# gps-to-spi.net
KiCad netlist of a schematic drawn in EAGLE
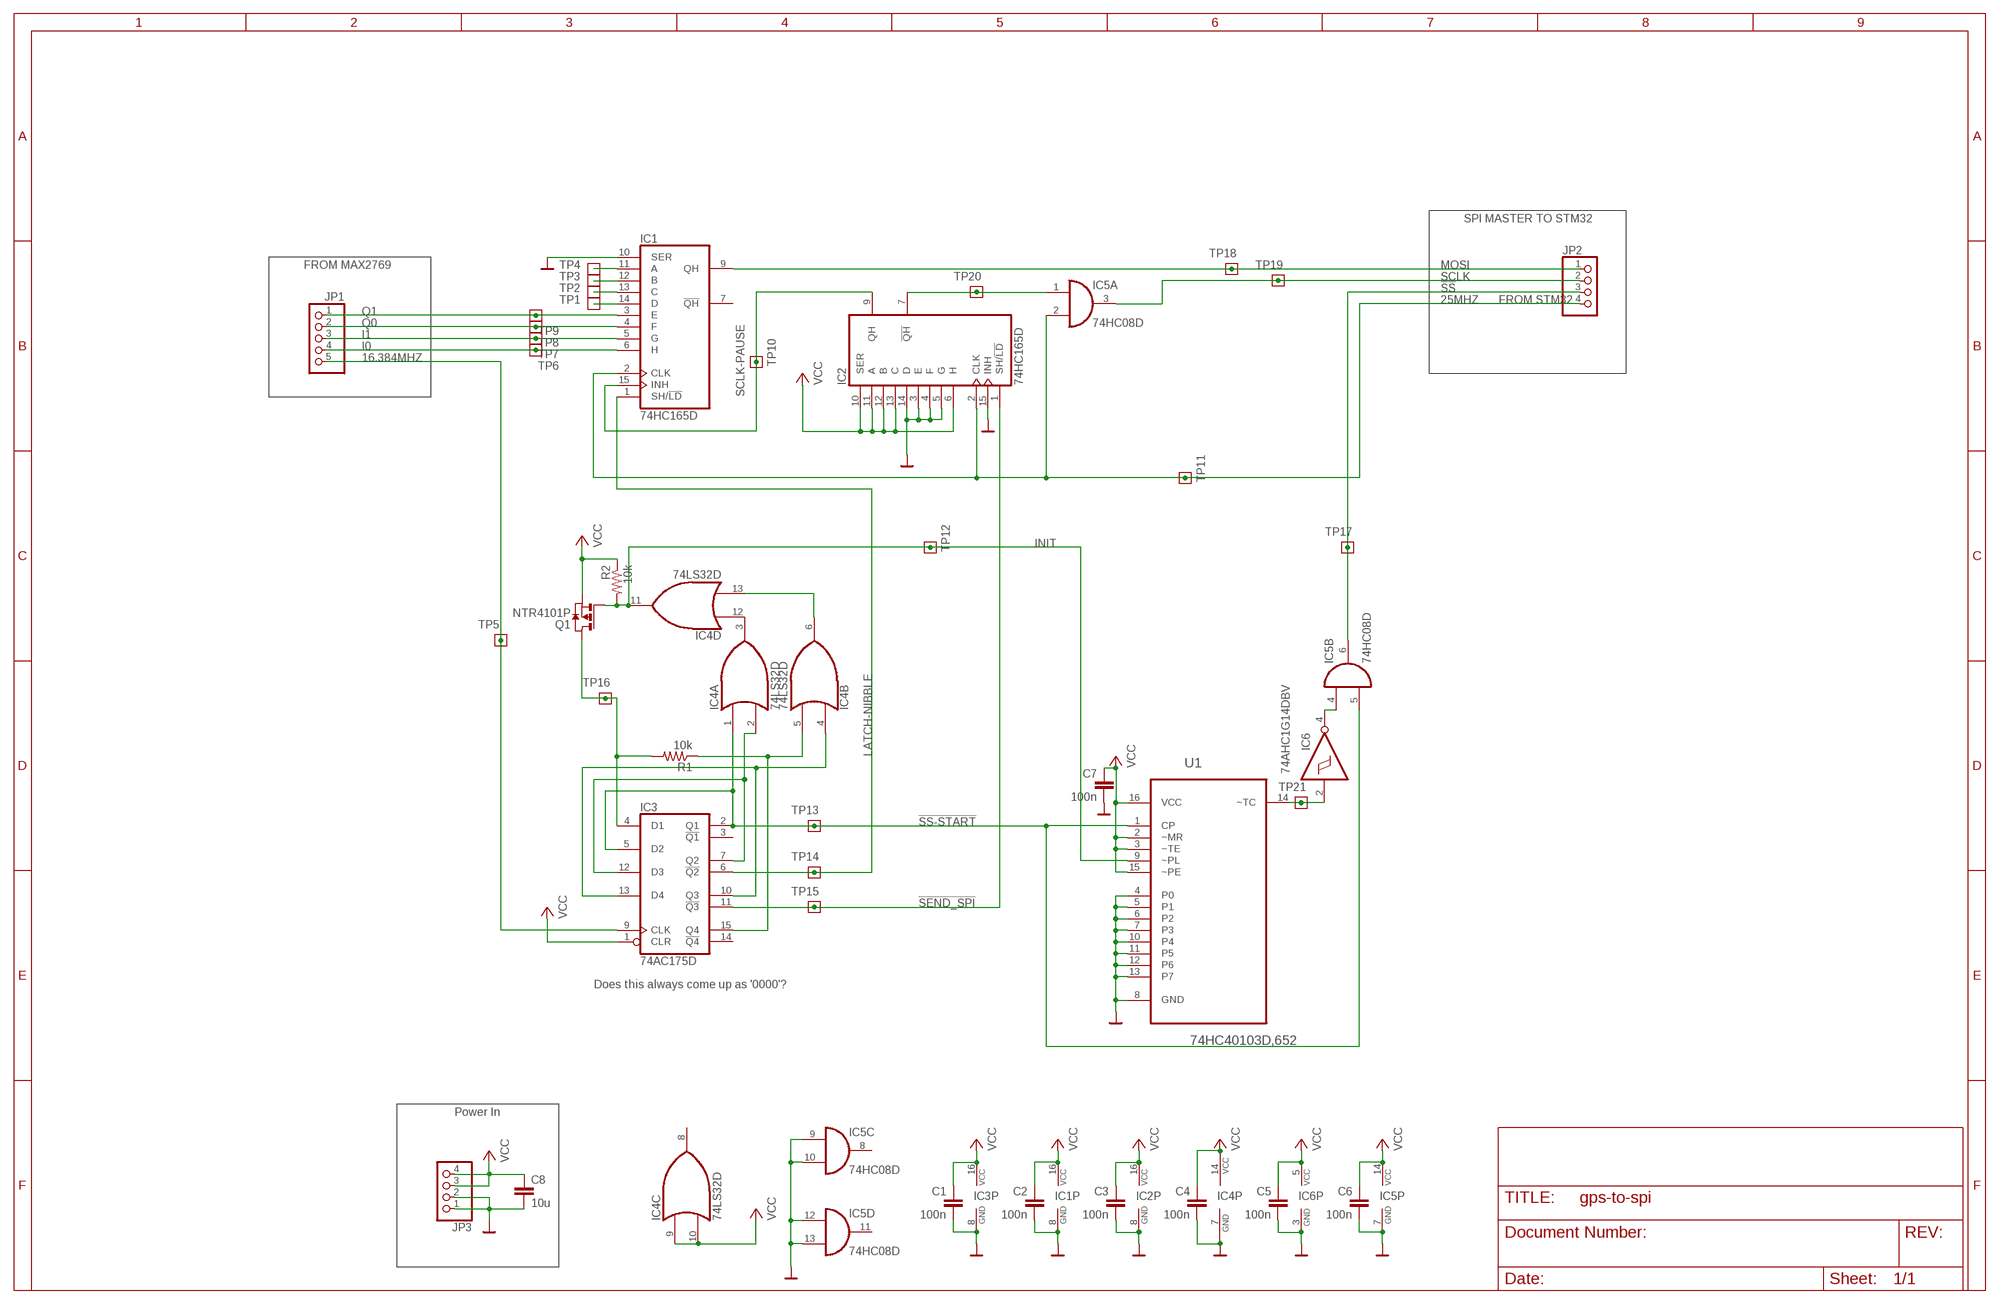
[diagram p0: schematic, sheet 1]

(export (version "E")
  (design (tool "Eeschema 10.0.6"))
  (components
    (comp (ref "C1")
      (value "100n")
      (footprint "eagle-import:.0603-B-NOSILK")
      (libsource (lib "eagle-import") (part "C-EU0603-B-NOSILK"))
    )
    (comp (ref "C2")
      (value "100n")
      (footprint "eagle-import:.0603-B-NOSILK")
      (libsource (lib "eagle-import") (part "C-EU0603-B-NOSILK"))
    )
    (comp (ref "C3")
      (value "100n")
      (footprint "eagle-import:.0603-B-NOSILK")
      (libsource (lib "eagle-import") (part "C-EU0603-B-NOSILK"))
    )
    (comp (ref "C4")
      (value "100n")
      (footprint "eagle-import:.0603-B-NOSILK")
      (libsource (lib "eagle-import") (part "C-EU0603-B-NOSILK"))
    )
    (comp (ref "C5")
      (value "100n")
      (footprint "eagle-import:.0603-B-NOSILK")
      (libsource (lib "eagle-import") (part "C-EU0603-B-NOSILK"))
    )
    (comp (ref "C6")
      (value "100n")
      (footprint "eagle-import:.0603-B-NOSILK")
      (libsource (lib "eagle-import") (part "C-EU0603-B-NOSILK"))
    )
    (comp (ref "C7")
      (value "100n")
      (footprint "eagle-import:.0603-B-NOSILK")
      (libsource (lib "eagle-import") (part "C-EU0603-B-NOSILK"))
    )
    (comp (ref "C8")
      (value "10u")
      (footprint "eagle-import:.0603-B-NOSILK")
      (libsource (lib "eagle-import") (part "C-EU0603-B-NOSILK"))
    )
    (comp (ref "IC1")
      (value "74HC165D")
      (footprint "eagle-import:SO16")
      (libsource (lib "eagle-import") (part "74165DHC"))
    )
    (comp (ref "IC2")
      (value "74HC165D")
      (footprint "eagle-import:SO16")
      (libsource (lib "eagle-import") (part "74165DHC"))
    )
    (comp (ref "IC3")
      (value "74AC175D")
      (footprint "eagle-import:SO16")
      (libsource (lib "eagle-import") (part "74175DAC"))
    )
    (comp (ref "IC4")
      (value "74LS32D")
      (footprint "eagle-import:SO14")
      (libsource (lib "eagle-import") (part "7432DLS"))
    )
    (comp (ref "IC5")
      (value "74HC08D")
      (footprint "eagle-import:SO14")
      (libsource (lib "eagle-import") (part "7408DHC"))
    )
    (comp (ref "IC6")
      (value "74AHC1G14DBV")
      (footprint "eagle-import:SOT23-5")
      (libsource (lib "eagle-import") (part "741G14DBVAHC"))
    )
    (comp (ref "JP1")
      (value "PINHD-1X5")
      (footprint "eagle-import:1X05")
      (libsource (lib "eagle-import") (part "PINHD-1X5"))
    )
    (comp (ref "JP2")
      (value "PINHD-1X4")
      (footprint "eagle-import:1X04")
      (libsource (lib "eagle-import") (part "PINHD-1X4"))
    )
    (comp (ref "JP3")
      (value "PINHD-1X4")
      (footprint "eagle-import:1X04")
      (libsource (lib "eagle-import") (part "PINHD-1X4"))
    )
    (comp (ref "Q1")
      (value "NTR4101P")
      (footprint "eagle-import:SOT23")
      (libsource (lib "eagle-import") (part "NTR4101P"))
    )
    (comp (ref "R1")
      (value "10k")
      (footprint "eagle-import:.0603-B-NOSILK")
      (libsource (lib "eagle-import") (part "R-US_0603-B-NOSILK"))
    )
    (comp (ref "R2")
      (value "10k")
      (footprint "eagle-import:.0603-B-NOSILK")
      (libsource (lib "eagle-import") (part "R-US_0603-B-NOSILK"))
    )
    (comp (ref "TP1")
      (value "TEST-POINT")
      (footprint "eagle-import:2MM-TEST-POINT")
      (libsource (lib "eagle-import") (part "TEST-POINT"))
    )
    (comp (ref "TP2")
      (value "TEST-POINT")
      (footprint "eagle-import:2MM-TEST-POINT")
      (libsource (lib "eagle-import") (part "TEST-POINT"))
    )
    (comp (ref "TP3")
      (value "TEST-POINT")
      (footprint "eagle-import:2MM-TEST-POINT")
      (libsource (lib "eagle-import") (part "TEST-POINT"))
    )
    (comp (ref "TP4")
      (value "TEST-POINT")
      (footprint "eagle-import:2MM-TEST-POINT")
      (libsource (lib "eagle-import") (part "TEST-POINT"))
    )
    (comp (ref "TP5")
      (value "TEST-POINT")
      (footprint "eagle-import:2MM-TEST-POINT")
      (libsource (lib "eagle-import") (part "TEST-POINT"))
    )
    (comp (ref "TP6")
      (value "TEST-POINT")
      (footprint "eagle-import:2MM-TEST-POINT")
      (libsource (lib "eagle-import") (part "TEST-POINT"))
    )
    (comp (ref "TP7")
      (value "TEST-POINT")
      (footprint "eagle-import:2MM-TEST-POINT")
      (libsource (lib "eagle-import") (part "TEST-POINT"))
    )
    (comp (ref "TP8")
      (value "TEST-POINT")
      (footprint "eagle-import:2MM-TEST-POINT")
      (libsource (lib "eagle-import") (part "TEST-POINT"))
    )
    (comp (ref "TP9")
      (value "TEST-POINT")
      (footprint "eagle-import:2MM-TEST-POINT")
      (libsource (lib "eagle-import") (part "TEST-POINT"))
    )
    (comp (ref "TP10")
      (value "TEST-POINT")
      (footprint "eagle-import:2MM-TEST-POINT")
      (libsource (lib "eagle-import") (part "TEST-POINT"))
    )
    (comp (ref "TP11")
      (value "TEST-POINT")
      (footprint "eagle-import:2MM-TEST-POINT")
      (libsource (lib "eagle-import") (part "TEST-POINT"))
    )
    (comp (ref "TP12")
      (value "TEST-POINT")
      (footprint "eagle-import:2MM-TEST-POINT")
      (libsource (lib "eagle-import") (part "TEST-POINT"))
    )
    (comp (ref "TP13")
      (value "TEST-POINT")
      (footprint "eagle-import:2MM-TEST-POINT")
      (libsource (lib "eagle-import") (part "TEST-POINT"))
    )
    (comp (ref "TP14")
      (value "TEST-POINT")
      (footprint "eagle-import:2MM-TEST-POINT")
      (libsource (lib "eagle-import") (part "TEST-POINT"))
    )
    (comp (ref "TP15")
      (value "TEST-POINT")
      (footprint "eagle-import:2MM-TEST-POINT")
      (libsource (lib "eagle-import") (part "TEST-POINT"))
    )
    (comp (ref "TP16")
      (value "TEST-POINT")
      (footprint "eagle-import:2MM-TEST-POINT")
      (libsource (lib "eagle-import") (part "TEST-POINT"))
    )
    (comp (ref "TP17")
      (value "TEST-POINT")
      (footprint "eagle-import:2MM-TEST-POINT")
      (libsource (lib "eagle-import") (part "TEST-POINT"))
    )
    (comp (ref "TP18")
      (value "TEST-POINT")
      (footprint "eagle-import:2MM-TEST-POINT")
      (libsource (lib "eagle-import") (part "TEST-POINT"))
    )
    (comp (ref "TP19")
      (value "TEST-POINT")
      (footprint "eagle-import:2MM-TEST-POINT")
      (libsource (lib "eagle-import") (part "TEST-POINT"))
    )
    (comp (ref "TP20")
      (value "TEST-POINT")
      (footprint "eagle-import:2MM-TEST-POINT")
      (libsource (lib "eagle-import") (part "TEST-POINT"))
    )
    (comp (ref "TP21")
      (value "TEST-POINT")
      (footprint "eagle-import:2MM-TEST-POINT")
      (libsource (lib "eagle-import") (part "TEST-POINT"))
    )
    (comp (ref "U1")
      (value "74HC40103D,652")
      (footprint "eagle-import:SOIC127P600X175-16N")
      (libsource (lib "eagle-import") (part "74HC40103D,652"))
    )
  )
  (nets
    (net (code "1") (name "/16.384MHZ") (class "Default")
      (node (ref "IC3") (pin "9") (pinfunction "CLK_9") (pintype "input"))
      (node (ref "JP1") (pin "5") (pinfunction "5_5") (pintype "passive"))
      (node (ref "TP5") (pin "1") (pinfunction "1_1") (pintype "passive"))
    )
    (net (code "2") (name "/25MHZ") (class "Default")
      (node (ref "IC1") (pin "2") (pinfunction "CLK_2") (pintype "input"))
      (node (ref "IC2") (pin "2") (pinfunction "CLK_2") (pintype "input"))
      (node (ref "IC5") (pin "2") (pinfunction "I1_2") (pintype "input"))
      (node (ref "JP2") (pin "4") (pinfunction "4_4") (pintype "passive"))
      (node (ref "TP11") (pin "1") (pinfunction "1_1") (pintype "passive"))
    )
    (net (code "3") (name "/I0") (class "Default")
      (node (ref "IC1") (pin "6") (pinfunction "H_6") (pintype "input"))
      (node (ref "JP1") (pin "4") (pinfunction "4_4") (pintype "passive"))
      (node (ref "TP6") (pin "1") (pinfunction "1_1") (pintype "passive"))
    )
    (net (code "4") (name "/I1") (class "Default")
      (node (ref "IC1") (pin "5") (pinfunction "G_5") (pintype "input"))
      (node (ref "JP1") (pin "3") (pinfunction "3_3") (pintype "passive"))
      (node (ref "TP7") (pin "1") (pinfunction "1_1") (pintype "passive"))
    )
    (net (code "5") (name "/INIT") (class "Default")
      (node (ref "IC4") (pin "11") (pinfunction "O_11") (pintype "output"))
      (node (ref "Q1") (pin "1") (pinfunction "G_1") (pintype "passive"))
      (node (ref "R2") (pin "2") (pinfunction "2_2") (pintype "passive"))
      (node (ref "TP12") (pin "1") (pinfunction "1_1") (pintype "passive"))
      (node (ref "U1") (pin "9") (pinfunction "~{PL}_9") (pintype "input"))
    )
    (net (code "6") (name "/LATCH-NIBBLE") (class "Default")
      (node (ref "IC1") (pin "1") (pinfunction "SH/~{LD}_1") (pintype "input"))
      (node (ref "IC3") (pin "6") (pinfunction "~{Q2}_6") (pintype "output"))
      (node (ref "TP14") (pin "1") (pinfunction "1_1") (pintype "passive"))
    )
    (net (code "7") (name "/MOSI") (class "Default")
      (node (ref "IC1") (pin "9") (pinfunction "QH_9") (pintype "output"))
      (node (ref "JP2") (pin "1") (pinfunction "1_1") (pintype "passive"))
      (node (ref "TP18") (pin "1") (pinfunction "1_1") (pintype "passive"))
    )
    (net (code "8") (name "/Q0") (class "Default")
      (node (ref "IC1") (pin "4") (pinfunction "F_4") (pintype "input"))
      (node (ref "JP1") (pin "2") (pinfunction "2_2") (pintype "passive"))
      (node (ref "TP8") (pin "1") (pinfunction "1_1") (pintype "passive"))
    )
    (net (code "9") (name "/Q1") (class "Default")
      (node (ref "IC1") (pin "3") (pinfunction "E_3") (pintype "input"))
      (node (ref "JP1") (pin "1") (pinfunction "1_1") (pintype "passive"))
      (node (ref "TP9") (pin "1") (pinfunction "1_1") (pintype "passive"))
    )
    (net (code "10") (name "/SCLK") (class "Default")
      (node (ref "IC5") (pin "3") (pinfunction "O_3") (pintype "output"))
      (node (ref "JP2") (pin "2") (pinfunction "2_2") (pintype "passive"))
      (node (ref "TP19") (pin "1") (pinfunction "1_1") (pintype "passive"))
    )
    (net (code "11") (name "/SCLK-PAUSE") (class "Default")
      (node (ref "IC1") (pin "15") (pinfunction "INH_15") (pintype "input"))
      (node (ref "IC2") (pin "9") (pinfunction "QH_9") (pintype "output"))
      (node (ref "TP10") (pin "1") (pinfunction "1_1") (pintype "passive"))
    )
    (net (code "12") (name "/~{SEND_SPI}") (class "Default")
      (node (ref "IC2") (pin "1") (pinfunction "SH/~{LD}_1") (pintype "input"))
      (node (ref "IC3") (pin "11") (pinfunction "~{Q3}_11") (pintype "output"))
      (node (ref "TP15") (pin "1") (pinfunction "1_1") (pintype "passive"))
    )
    (net (code "13") (name "/~{SS-START}") (class "Default")
      (node (ref "IC3") (pin "2") (pinfunction "Q1_2") (pintype "output"))
      (node (ref "IC3") (pin "5") (pinfunction "D2_5") (pintype "input"))
      (node (ref "IC4") (pin "1") (pinfunction "I0_1") (pintype "input"))
      (node (ref "IC5") (pin "5") (pinfunction "I1_5") (pintype "input"))
      (node (ref "TP13") (pin "1") (pinfunction "1_1") (pintype "passive"))
      (node (ref "U1") (pin "1") (pinfunction "CP_1") (pintype "input"))
    )
    (net (code "14") (name "/~{SS}") (class "Default")
      (node (ref "IC5") (pin "6") (pinfunction "O_6") (pintype "output"))
      (node (ref "JP2") (pin "3") (pinfunction "3_3") (pintype "passive"))
      (node (ref "TP17") (pin "1") (pinfunction "1_1") (pintype "passive"))
    )
    (net (code "15") (name "GND") (class "Default")
      (node (ref "C1") (pin "2") (pinfunction "2_2") (pintype "passive"))
      (node (ref "C2") (pin "2") (pinfunction "2_2") (pintype "passive"))
      (node (ref "C3") (pin "2") (pinfunction "2_2") (pintype "passive"))
      (node (ref "C4") (pin "2") (pinfunction "2_2") (pintype "passive"))
      (node (ref "C5") (pin "2") (pinfunction "2_2") (pintype "passive"))
      (node (ref "C6") (pin "2") (pinfunction "2_2") (pintype "passive"))
      (node (ref "C7") (pin "2") (pinfunction "2_2") (pintype "passive"))
      (node (ref "C8") (pin "2") (pinfunction "2_2") (pintype "passive"))
      (node (ref "IC1") (pin "10") (pinfunction "SER_10") (pintype "input"))
      (node (ref "IC1") (pin "8") (pinfunction "GND_8") (pintype "power_in"))
      (node (ref "IC2") (pin "14") (pinfunction "D_14") (pintype "input"))
      (node (ref "IC2") (pin "15") (pinfunction "INH_15") (pintype "input"))
      (node (ref "IC2") (pin "3") (pinfunction "E_3") (pintype "input"))
      (node (ref "IC2") (pin "4") (pinfunction "F_4") (pintype "input"))
      (node (ref "IC2") (pin "5") (pinfunction "G_5") (pintype "input"))
      (node (ref "IC2") (pin "8") (pinfunction "GND_8") (pintype "power_in"))
      (node (ref "IC3") (pin "8") (pinfunction "GND_8") (pintype "power_in"))
      (node (ref "IC4") (pin "7") (pinfunction "GND_7") (pintype "power_in"))
      (node (ref "IC5") (pin "10") (pinfunction "I1_10") (pintype "input"))
      (node (ref "IC5") (pin "12") (pinfunction "I0_12") (pintype "input"))
      (node (ref "IC5") (pin "13") (pinfunction "I1_13") (pintype "input"))
      (node (ref "IC5") (pin "7") (pinfunction "GND_7") (pintype "power_in"))
      (node (ref "IC5") (pin "9") (pinfunction "I0_9") (pintype "input"))
      (node (ref "IC6") (pin "3") (pinfunction "GND_3") (pintype "power_in"))
      (node (ref "JP3") (pin "1") (pinfunction "1_1") (pintype "passive"))
      (node (ref "JP3") (pin "2") (pinfunction "2_2") (pintype "passive"))
      (node (ref "U1") (pin "10") (pinfunction "P4_10") (pintype "input"))
      (node (ref "U1") (pin "11") (pinfunction "P5_11") (pintype "input"))
      (node (ref "U1") (pin "12") (pinfunction "P6_12") (pintype "input"))
      (node (ref "U1") (pin "13") (pinfunction "P7_13") (pintype "input"))
      (node (ref "U1") (pin "4") (pinfunction "P0_4") (pintype "input"))
      (node (ref "U1") (pin "5") (pinfunction "P1_5") (pintype "input"))
      (node (ref "U1") (pin "6") (pinfunction "P2_6") (pintype "input"))
      (node (ref "U1") (pin "7") (pinfunction "P3_7") (pintype "input"))
      (node (ref "U1") (pin "8") (pinfunction "GND_8") (pintype "passive"))
    )
    (net (code "16") (name "Net-(IC1A-A)") (class "Default")
      (node (ref "IC1") (pin "11") (pinfunction "A_11") (pintype "input"))
      (node (ref "TP4") (pin "1") (pinfunction "1_1") (pintype "passive"))
    )
    (net (code "17") (name "Net-(IC1A-B)") (class "Default")
      (node (ref "IC1") (pin "12") (pinfunction "B_12") (pintype "input"))
      (node (ref "TP3") (pin "1") (pinfunction "1_1") (pintype "passive"))
    )
    (net (code "18") (name "Net-(IC1A-C)") (class "Default")
      (node (ref "IC1") (pin "13") (pinfunction "C_13") (pintype "input"))
      (node (ref "TP2") (pin "1") (pinfunction "1_1") (pintype "passive"))
    )
    (net (code "19") (name "Net-(IC1A-D)") (class "Default")
      (node (ref "IC1") (pin "14") (pinfunction "D_14") (pintype "input"))
      (node (ref "TP1") (pin "1") (pinfunction "1_1") (pintype "passive"))
    )
    (net (code "20") (name "Net-(IC2A-~{QH})") (class "Default")
      (node (ref "IC2") (pin "7") (pinfunction "~{QH}_7") (pintype "output"))
      (node (ref "IC5") (pin "1") (pinfunction "I0_1") (pintype "input"))
      (node (ref "TP20") (pin "1") (pinfunction "1_1") (pintype "passive"))
    )
    (net (code "21") (name "Net-(IC3A-D1)") (class "Default")
      (node (ref "IC3") (pin "4") (pinfunction "D1_4") (pintype "input"))
      (node (ref "Q1") (pin "3") (pinfunction "D_3") (pintype "passive"))
      (node (ref "R1") (pin "2") (pinfunction "2_2") (pintype "passive"))
      (node (ref "TP16") (pin "1") (pinfunction "1_1") (pintype "passive"))
    )
    (net (code "22") (name "Net-(IC3A-D3)") (class "Default")
      (node (ref "IC3") (pin "12") (pinfunction "D3_12") (pintype "input"))
      (node (ref "IC3") (pin "7") (pinfunction "Q2_7") (pintype "output"))
      (node (ref "IC4") (pin "2") (pinfunction "I1_2") (pintype "input"))
    )
    (net (code "23") (name "Net-(IC3A-D4)") (class "Default")
      (node (ref "IC3") (pin "10") (pinfunction "Q3_10") (pintype "output"))
      (node (ref "IC3") (pin "13") (pinfunction "D4_13") (pintype "input"))
      (node (ref "IC4") (pin "4") (pinfunction "I0_4") (pintype "input"))
    )
    (net (code "24") (name "Net-(IC3A-Q4)") (class "Default")
      (node (ref "IC3") (pin "15") (pinfunction "Q4_15") (pintype "output"))
      (node (ref "IC4") (pin "5") (pinfunction "I1_5") (pintype "input"))
      (node (ref "R1") (pin "1") (pinfunction "1_1") (pintype "passive"))
    )
    (net (code "25") (name "Net-(IC4A-O)") (class "Default")
      (node (ref "IC4") (pin "12") (pinfunction "I0_12") (pintype "input"))
      (node (ref "IC4") (pin "3") (pinfunction "O_3") (pintype "output"))
    )
    (net (code "26") (name "Net-(IC4B-O)") (class "Default")
      (node (ref "IC4") (pin "13") (pinfunction "I1_13") (pintype "input"))
      (node (ref "IC4") (pin "6") (pinfunction "O_6") (pintype "output"))
    )
    (net (code "27") (name "Net-(IC5B-I0)") (class "Default")
      (node (ref "IC5") (pin "4") (pinfunction "I0_4") (pintype "input"))
      (node (ref "IC6") (pin "4") (pinfunction "O_4") (pintype "output"))
    )
    (net (code "28") (name "Net-(IC6A-I)") (class "Default")
      (node (ref "IC6") (pin "2") (pinfunction "I_2") (pintype "input"))
      (node (ref "TP21") (pin "1") (pinfunction "1_1") (pintype "passive"))
      (node (ref "U1") (pin "14") (pinfunction "~{TC}_14") (pintype "output"))
    )
    (net (code "29") (name "VCC") (class "Default")
      (node (ref "C1") (pin "1") (pinfunction "1_1") (pintype "passive"))
      (node (ref "C2") (pin "1") (pinfunction "1_1") (pintype "passive"))
      (node (ref "C3") (pin "1") (pinfunction "1_1") (pintype "passive"))
      (node (ref "C4") (pin "1") (pinfunction "1_1") (pintype "passive"))
      (node (ref "C5") (pin "1") (pinfunction "1_1") (pintype "passive"))
      (node (ref "C6") (pin "1") (pinfunction "1_1") (pintype "passive"))
      (node (ref "C7") (pin "1") (pinfunction "1_1") (pintype "passive"))
      (node (ref "C8") (pin "1") (pinfunction "1_1") (pintype "passive"))
      (node (ref "IC1") (pin "16") (pinfunction "VCC_16") (pintype "power_in"))
      (node (ref "IC2") (pin "10") (pinfunction "SER_10") (pintype "input"))
      (node (ref "IC2") (pin "11") (pinfunction "A_11") (pintype "input"))
      (node (ref "IC2") (pin "12") (pinfunction "B_12") (pintype "input"))
      (node (ref "IC2") (pin "13") (pinfunction "C_13") (pintype "input"))
      (node (ref "IC2") (pin "16") (pinfunction "VCC_16") (pintype "power_in"))
      (node (ref "IC2") (pin "6") (pinfunction "H_6") (pintype "input"))
      (node (ref "IC3") (pin "1") (pinfunction "CLR_1") (pintype "input"))
      (node (ref "IC3") (pin "16") (pinfunction "VCC_16") (pintype "power_in"))
      (node (ref "IC4") (pin "10") (pinfunction "I1_10") (pintype "input"))
      (node (ref "IC4") (pin "14") (pinfunction "VCC_14") (pintype "power_in"))
      (node (ref "IC4") (pin "9") (pinfunction "I0_9") (pintype "input"))
      (node (ref "IC5") (pin "14") (pinfunction "VCC_14") (pintype "power_in"))
      (node (ref "IC6") (pin "5") (pinfunction "VCC_5") (pintype "power_in"))
      (node (ref "JP3") (pin "3") (pinfunction "3_3") (pintype "passive"))
      (node (ref "JP3") (pin "4") (pinfunction "4_4") (pintype "passive"))
      (node (ref "Q1") (pin "2") (pinfunction "S_2") (pintype "passive"))
      (node (ref "R2") (pin "1") (pinfunction "1_1") (pintype "passive"))
      (node (ref "U1") (pin "15") (pinfunction "~{PE}_15") (pintype "input"))
      (node (ref "U1") (pin "16") (pinfunction "VCC_16") (pintype "power_in"))
      (node (ref "U1") (pin "2") (pinfunction "~{MR}_2") (pintype "input"))
      (node (ref "U1") (pin "3") (pinfunction "~{TE}_3") (pintype "input"))
    )
    (net (code "30") (name "unconnected-(IC1A-~{QH}-Pad7)") (class "Default")
      (node (ref "IC1") (pin "7") (pinfunction "~{QH}_7") (pintype "output"))
    )
    (net (code "31") (name "unconnected-(IC3A-~{Q1}-Pad3)") (class "Default")
      (node (ref "IC3") (pin "3") (pinfunction "~{Q1}_3") (pintype "output"))
    )
    (net (code "32") (name "unconnected-(IC3A-~{Q4}-Pad14)") (class "Default")
      (node (ref "IC3") (pin "14") (pinfunction "~{Q4}_14") (pintype "output"))
    )
    (net (code "33") (name "unconnected-(IC4C-O-Pad8)") (class "Default")
      (node (ref "IC4") (pin "8") (pinfunction "O_8") (pintype "output"))
    )
    (net (code "34") (name "unconnected-(IC5C-O-Pad8)") (class "Default")
      (node (ref "IC5") (pin "8") (pinfunction "O_8") (pintype "output"))
    )
    (net (code "35") (name "unconnected-(IC5D-O-Pad11)") (class "Default")
      (node (ref "IC5") (pin "11") (pinfunction "O_11") (pintype "output"))
    )
  )
)
